# circle2.net
KiCad netlist of a schematic drawn in EAGLE
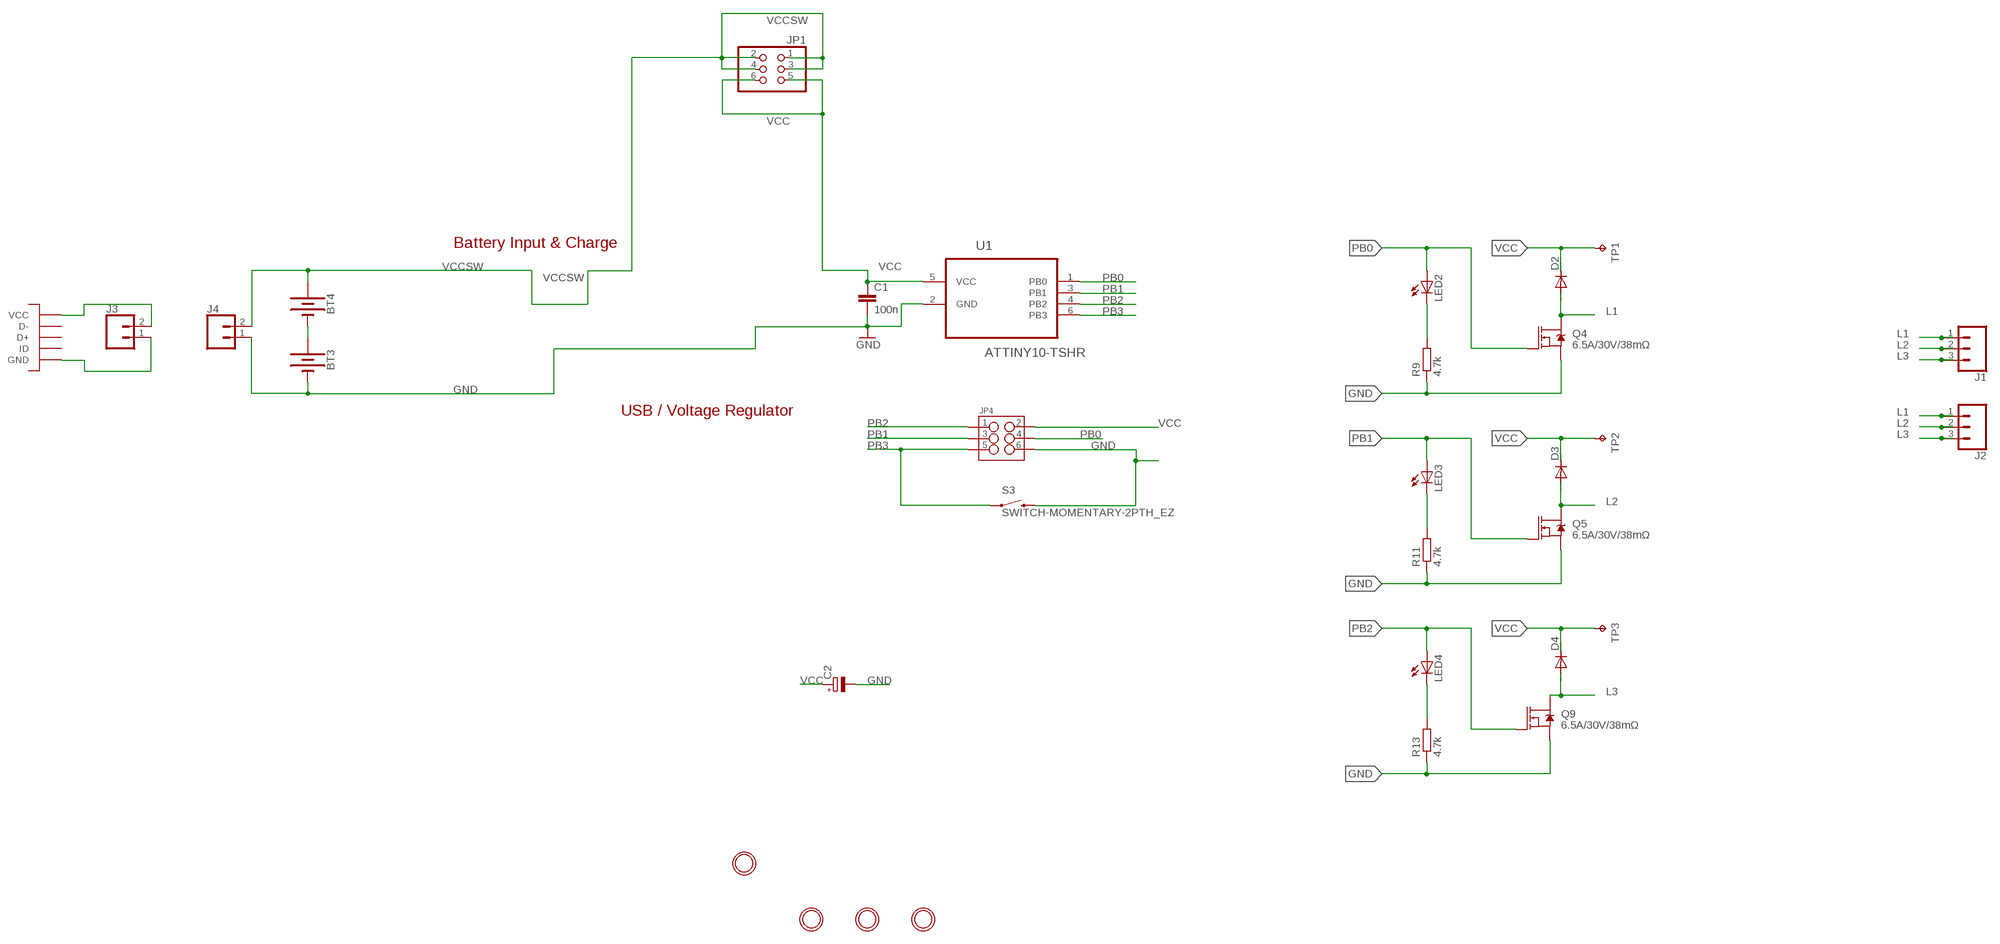
[diagram p0: schematic, sheet 1]

(export (version "E")
  (design (tool "Eeschema 10.0.6"))
  (components
    (comp (ref "BT3")
      (value "BATTERY-AA_KIT")
      (footprint "eagle-import:BATTERY-AA-KIT")
      (libsource (lib "eagle-import") (part "BATTERY-AA_KIT"))
    )
    (comp (ref "BT4")
      (value "BATTERY-AA_KIT")
      (footprint "eagle-import:BATTERY-AA-KIT")
      (libsource (lib "eagle-import") (part "BATTERY-AA_KIT"))
    )
    (comp (ref "C1")
      (value "100n")
      (footprint "eagle-import:0805")
      (libsource (lib "eagle-import") (part "CAP0805"))
    )
    (comp (ref "C2")
      (value "CPOL-EUA")
      (footprint "eagle-import:PANASONIC_A")
      (libsource (lib "eagle-import") (part "CPOL-EUA"))
    )
    (comp (ref "D2")
      (value "DIODE-DO214AC")
      (footprint "eagle-import:DO214AC")
      (libsource (lib "eagle-import") (part "DIODE-DO214AC"))
    )
    (comp (ref "D3")
      (value "DIODE-DO214AC")
      (footprint "eagle-import:DO214AC")
      (libsource (lib "eagle-import") (part "DIODE-DO214AC"))
    )
    (comp (ref "D4")
      (value "DIODE-DO214AC")
      (footprint "eagle-import:DO214AC")
      (libsource (lib "eagle-import") (part "DIODE-DO214AC"))
    )
    (comp (ref "J1")
      (value "CONN_031X03_NO_SILK")
      (footprint "eagle-import:1X03_NO_SILK")
      (libsource (lib "eagle-import") (part "CONN_031X03_NO_SILK"))
    )
    (comp (ref "J2")
      (value "CONN_031X03_NO_SILK")
      (footprint "eagle-import:1X03_NO_SILK")
      (libsource (lib "eagle-import") (part "CONN_031X03_NO_SILK"))
    )
    (comp (ref "J3")
      (value "CONN_02LOCK_LONGPADS")
      (footprint "eagle-import:1X02_LOCK_LONGPADS")
      (libsource (lib "eagle-import") (part "CONN_02LOCK_LONGPADS"))
    )
    (comp (ref "J4")
      (value "CONN_02LOCK_LONGPADS")
      (footprint "eagle-import:1X02_LOCK_LONGPADS")
      (libsource (lib "eagle-import") (part "CONN_02LOCK_LONGPADS"))
    )
    (comp (ref "JP1")
      (value "PINHD-2X3")
      (footprint "eagle-import:2X03")
      (libsource (lib "eagle-import") (part "PINHD-2X3"))
    )
    (comp (ref "JP4")
      (value "M03X2NO_SILK")
      (footprint "eagle-import:2X3-NS")
      (libsource (lib "eagle-import") (part "M03X2NO_SILK"))
    )
    (comp (ref "LED2")
      (value "LEDKA-3528ASYC")
      (footprint "eagle-import:KA-3528ASYC")
      (libsource (lib "eagle-import") (part "LEDKA-3528ASYC"))
    )
    (comp (ref "LED3")
      (value "LEDKA-3528ASYC")
      (footprint "eagle-import:KA-3528ASYC")
      (libsource (lib "eagle-import") (part "LEDKA-3528ASYC"))
    )
    (comp (ref "LED4")
      (value "LEDKA-3528ASYC")
      (footprint "eagle-import:KA-3528ASYC")
      (libsource (lib "eagle-import") (part "LEDKA-3528ASYC"))
    )
    (comp (ref "Q4")
      (value "6.5A/30V/38mΩ")
      (footprint "eagle-import:SO08")
      (libsource (lib "eagle-import") (part "MOSFET-NCH-FDS6630A"))
    )
    (comp (ref "Q5")
      (value "6.5A/30V/38mΩ")
      (footprint "eagle-import:SO08")
      (libsource (lib "eagle-import") (part "MOSFET-NCH-FDS6630A"))
    )
    (comp (ref "Q9")
      (value "6.5A/30V/38mΩ")
      (footprint "eagle-import:SO08")
      (libsource (lib "eagle-import") (part "MOSFET-NCH-FDS6630A"))
    )
    (comp (ref "R9")
      (value "4.7k")
      (footprint "eagle-import:R0603")
      (libsource (lib "eagle-import") (part "R-EU_R0603"))
    )
    (comp (ref "R11")
      (value "4.7k")
      (footprint "eagle-import:R0603")
      (libsource (lib "eagle-import") (part "R-EU_R0603"))
    )
    (comp (ref "R13")
      (value "4.7k")
      (footprint "eagle-import:R0603")
      (libsource (lib "eagle-import") (part "R-EU_R0603"))
    )
    (comp (ref "S3")
      (value "SWITCH-MOMENTARY-2PTH_EZ")
      (footprint "eagle-import:TACTILE-PTH-EZ")
      (libsource (lib "eagle-import") (part "SWITCH-MOMENTARY-2PTH_EZ"))
    )
    (comp (ref "TP1")
      (value "TPTP20SQ")
      (footprint "eagle-import:TP20SQ")
      (libsource (lib "eagle-import") (part "TPTP20SQ"))
    )
    (comp (ref "TP2")
      (value "TPTP20SQ")
      (footprint "eagle-import:TP20SQ")
      (libsource (lib "eagle-import") (part "TPTP20SQ"))
    )
    (comp (ref "TP3")
      (value "TPTP20SQ")
      (footprint "eagle-import:TP20SQ")
      (libsource (lib "eagle-import") (part "TPTP20SQ"))
    )
    (comp (ref "U$1")
      (value "MOUNTINGHOLE2.0")
      (footprint "eagle-import:MOUNTINGHOLE_2.0_PLATED")
      (libsource (lib "eagle-import") (part "MOUNTINGHOLE2.0"))
    )
    (comp (ref "U$2")
      (value "MOUNTINGHOLE2.0")
      (footprint "eagle-import:MOUNTINGHOLE_2.0_PLATED")
      (libsource (lib "eagle-import") (part "MOUNTINGHOLE2.0"))
    )
    (comp (ref "U$3")
      (value "MOUNTINGHOLE2.0")
      (footprint "eagle-import:MOUNTINGHOLE_2.0_PLATED")
      (libsource (lib "eagle-import") (part "MOUNTINGHOLE2.0"))
    )
    (comp (ref "U$5")
      (value "MICROUSB")
      (footprint "eagle-import:MICRO_B")
      (libsource (lib "eagle-import") (part "MICROUSB"))
    )
    (comp (ref "U$7")
      (value "MOUNTINGHOLE2.0")
      (footprint "eagle-import:MOUNTINGHOLE_2.0_PLATED")
      (libsource (lib "eagle-import") (part "MOUNTINGHOLE2.0"))
    )
    (comp (ref "U1")
      (value "ATTINY10-TSHR")
      (footprint "eagle-import:SOT95P280X145-6N")
      (libsource (lib "eagle-import") (part "ATTINY10-TSHR"))
    )
  )
  (nets
    (net (code "1") (name "/L1") (class "Default")
      (node (ref "D2") (pin "A") (pinfunction "A_A") (pintype "passive"))
      (node (ref "J1") (pin "1") (pinfunction "1_1") (pintype "passive"))
      (node (ref "J2") (pin "1") (pinfunction "1_1") (pintype "passive"))
      (node (ref "Q4") (pin "5") (pinfunction "D_5") (pintype "bidirectional"))
      (node (ref "Q4") (pin "6") (pinfunction "D_6") (pintype "bidirectional"))
      (node (ref "Q4") (pin "7") (pinfunction "D_7") (pintype "bidirectional"))
      (node (ref "Q4") (pin "8") (pinfunction "D_8") (pintype "bidirectional"))
    )
    (net (code "2") (name "/L2") (class "Default")
      (node (ref "D3") (pin "A") (pinfunction "A_A") (pintype "passive"))
      (node (ref "J1") (pin "2") (pinfunction "2_2") (pintype "passive"))
      (node (ref "J2") (pin "2") (pinfunction "2_2") (pintype "passive"))
      (node (ref "Q5") (pin "5") (pinfunction "D_5") (pintype "bidirectional"))
      (node (ref "Q5") (pin "6") (pinfunction "D_6") (pintype "bidirectional"))
      (node (ref "Q5") (pin "7") (pinfunction "D_7") (pintype "bidirectional"))
      (node (ref "Q5") (pin "8") (pinfunction "D_8") (pintype "bidirectional"))
    )
    (net (code "3") (name "/L3") (class "Default")
      (node (ref "D4") (pin "A") (pinfunction "A_A") (pintype "passive"))
      (node (ref "J1") (pin "3") (pinfunction "3_3") (pintype "passive"))
      (node (ref "J2") (pin "3") (pinfunction "3_3") (pintype "passive"))
      (node (ref "Q9") (pin "5") (pinfunction "D_5") (pintype "bidirectional"))
      (node (ref "Q9") (pin "6") (pinfunction "D_6") (pintype "bidirectional"))
      (node (ref "Q9") (pin "7") (pinfunction "D_7") (pintype "bidirectional"))
      (node (ref "Q9") (pin "8") (pinfunction "D_8") (pintype "bidirectional"))
    )
    (net (code "4") (name "/PB3") (class "Default")
      (node (ref "JP4") (pin "5") (pinfunction "5_5") (pintype "bidirectional"))
      (node (ref "S3") (pin "1") (pinfunction "1_1") (pintype "passive"))
      (node (ref "U1") (pin "6") (pinfunction "PB3_6") (pintype "bidirectional"))
    )
    (net (code "5") (name "/VCCSW") (class "Default")
      (node (ref "BT4") (pin "PWR@1") (pinfunction "+_PWR@1") (pintype "power_in"))
      (node (ref "J4") (pin "2") (pinfunction "2_2") (pintype "passive"))
      (node (ref "JP1") (pin "1") (pinfunction "1_1") (pintype "passive"))
      (node (ref "JP1") (pin "2") (pinfunction "2_2") (pintype "passive"))
      (node (ref "JP1") (pin "3") (pinfunction "3_3") (pintype "passive"))
      (node (ref "JP1") (pin "4") (pinfunction "4_4") (pintype "passive"))
    )
    (net (code "6") (name "GND") (class "Default")
      (node (ref "BT3") (pin "GND@1") (pinfunction "-_GND@1") (pintype "power_in"))
      (node (ref "C1") (pin "2") (pinfunction "2_2") (pintype "passive"))
      (node (ref "C2") (pin "-") (pinfunction "-_-") (pintype "passive"))
      (node (ref "J4") (pin "1") (pinfunction "1_1") (pintype "passive"))
      (node (ref "JP4") (pin "6") (pinfunction "6_6") (pintype "bidirectional"))
      (node (ref "Q4") (pin "1") (pinfunction "S_1") (pintype "bidirectional"))
      (node (ref "Q4") (pin "2") (pinfunction "S_2") (pintype "bidirectional"))
      (node (ref "Q4") (pin "3") (pinfunction "S_3") (pintype "bidirectional"))
      (node (ref "Q5") (pin "1") (pinfunction "S_1") (pintype "bidirectional"))
      (node (ref "Q5") (pin "2") (pinfunction "S_2") (pintype "bidirectional"))
      (node (ref "Q5") (pin "3") (pinfunction "S_3") (pintype "bidirectional"))
      (node (ref "Q9") (pin "1") (pinfunction "S_1") (pintype "bidirectional"))
      (node (ref "Q9") (pin "2") (pinfunction "S_2") (pintype "bidirectional"))
      (node (ref "Q9") (pin "3") (pinfunction "S_3") (pintype "bidirectional"))
      (node (ref "R11") (pin "1") (pinfunction "1_1") (pintype "passive"))
      (node (ref "R13") (pin "1") (pinfunction "1_1") (pintype "passive"))
      (node (ref "R9") (pin "1") (pinfunction "1_1") (pintype "passive"))
      (node (ref "S3") (pin "3") (pinfunction "2_3") (pintype "passive"))
      (node (ref "U1") (pin "2") (pinfunction "GND_2") (pintype "passive"))
    )
    (net (code "7") (name "Net-(BT3-+)") (class "Default")
      (node (ref "BT3") (pin "PWR@1") (pinfunction "+_PWR@1") (pintype "power_in"))
      (node (ref "BT4") (pin "GND@1") (pinfunction "-_GND@1") (pintype "power_in"))
    )
    (net (code "8") (name "Net-(J3-Pad1)") (class "Default")
      (node (ref "J3") (pin "1") (pinfunction "1_1") (pintype "passive"))
      (node (ref "U$5") (pin "GND1") (pinfunction "GND_GND1") (pintype "bidirectional"))
      (node (ref "U$5") (pin "GND2") (pinfunction "GND_GND2") (pintype "bidirectional"))
      (node (ref "U$5") (pin "GND3") (pinfunction "GND_GND3") (pintype "bidirectional"))
      (node (ref "U$5") (pin "GND4") (pinfunction "GND_GND4") (pintype "bidirectional"))
      (node (ref "U$5") (pin "GND7") (pinfunction "GND_GND7") (pintype "bidirectional"))
      (node (ref "U$5") (pin "GND8") (pinfunction "GND_GND8") (pintype "bidirectional"))
      (node (ref "U$5") (pin "P5") (pinfunction "GND_P5") (pintype "bidirectional"))
    )
    (net (code "9") (name "Net-(LED2-PadC)") (class "Default")
      (node (ref "LED2") (pin "C") (pinfunction "C_C") (pintype "passive"))
      (node (ref "R9") (pin "2") (pinfunction "2_2") (pintype "passive"))
    )
    (net (code "10") (name "Net-(LED3-PadC)") (class "Default")
      (node (ref "LED3") (pin "C") (pinfunction "C_C") (pintype "passive"))
      (node (ref "R11") (pin "2") (pinfunction "2_2") (pintype "passive"))
    )
    (net (code "11") (name "Net-(LED4-PadC)") (class "Default")
      (node (ref "LED4") (pin "C") (pinfunction "C_C") (pintype "passive"))
      (node (ref "R13") (pin "2") (pinfunction "2_2") (pintype "passive"))
    )
    (net (code "12") (name "Net-(U$5-VCC)") (class "Default")
      (node (ref "J3") (pin "2") (pinfunction "2_2") (pintype "passive"))
      (node (ref "U$5") (pin "P1") (pinfunction "VCC_P1") (pintype "bidirectional"))
    )
    (net (code "13") (name "PB0") (class "Default")
      (node (ref "JP4") (pin "4") (pinfunction "4_4") (pintype "bidirectional"))
      (node (ref "LED2") (pin "A") (pinfunction "A_A") (pintype "passive"))
      (node (ref "Q4") (pin "4") (pinfunction "G_4") (pintype "bidirectional"))
      (node (ref "U1") (pin "1") (pinfunction "PB0_1") (pintype "bidirectional"))
    )
    (net (code "14") (name "PB1") (class "Default")
      (node (ref "JP4") (pin "3") (pinfunction "3_3") (pintype "bidirectional"))
      (node (ref "LED3") (pin "A") (pinfunction "A_A") (pintype "passive"))
      (node (ref "Q5") (pin "4") (pinfunction "G_4") (pintype "bidirectional"))
      (node (ref "U1") (pin "3") (pinfunction "PB1_3") (pintype "bidirectional"))
    )
    (net (code "15") (name "PB2") (class "Default")
      (node (ref "JP4") (pin "1") (pinfunction "1_1") (pintype "bidirectional"))
      (node (ref "LED4") (pin "A") (pinfunction "A_A") (pintype "passive"))
      (node (ref "Q9") (pin "4") (pinfunction "G_4") (pintype "bidirectional"))
      (node (ref "U1") (pin "4") (pinfunction "PB2_4") (pintype "bidirectional"))
    )
    (net (code "16") (name "VCC") (class "Default")
      (node (ref "C1") (pin "1") (pinfunction "1_1") (pintype "passive"))
      (node (ref "C2") (pin "+") (pinfunction "+_+") (pintype "passive"))
      (node (ref "D2") (pin "C") (pinfunction "C_C") (pintype "passive"))
      (node (ref "D3") (pin "C") (pinfunction "C_C") (pintype "passive"))
      (node (ref "D4") (pin "C") (pinfunction "C_C") (pintype "passive"))
      (node (ref "JP1") (pin "5") (pinfunction "5_5") (pintype "passive"))
      (node (ref "JP1") (pin "6") (pinfunction "6_6") (pintype "passive"))
      (node (ref "JP4") (pin "2") (pinfunction "2_2") (pintype "bidirectional"))
      (node (ref "TP1") (pin "TP") (pinfunction "TP_TP") (pintype "input"))
      (node (ref "TP2") (pin "TP") (pinfunction "TP_TP") (pintype "input"))
      (node (ref "TP3") (pin "TP") (pinfunction "TP_TP") (pintype "input"))
      (node (ref "U1") (pin "5") (pinfunction "VCC_5") (pintype "power_in"))
    )
    (net (code "17") (name "unconnected-(U$5-D+-PadP3)") (class "Default")
      (node (ref "U$5") (pin "P3") (pinfunction "D+_P3") (pintype "bidirectional"))
    )
    (net (code "18") (name "unconnected-(U$5-D--PadP2)") (class "Default")
      (node (ref "U$5") (pin "P2") (pinfunction "D-_P2") (pintype "bidirectional"))
    )
    (net (code "19") (name "unconnected-(U$5-ID-PadP4)") (class "Default")
      (node (ref "U$5") (pin "P4") (pinfunction "ID_P4") (pintype "bidirectional"))
    )
  )
)
